# senior_project_rev4.net
KiCad netlist of a schematic drawn in EAGLE
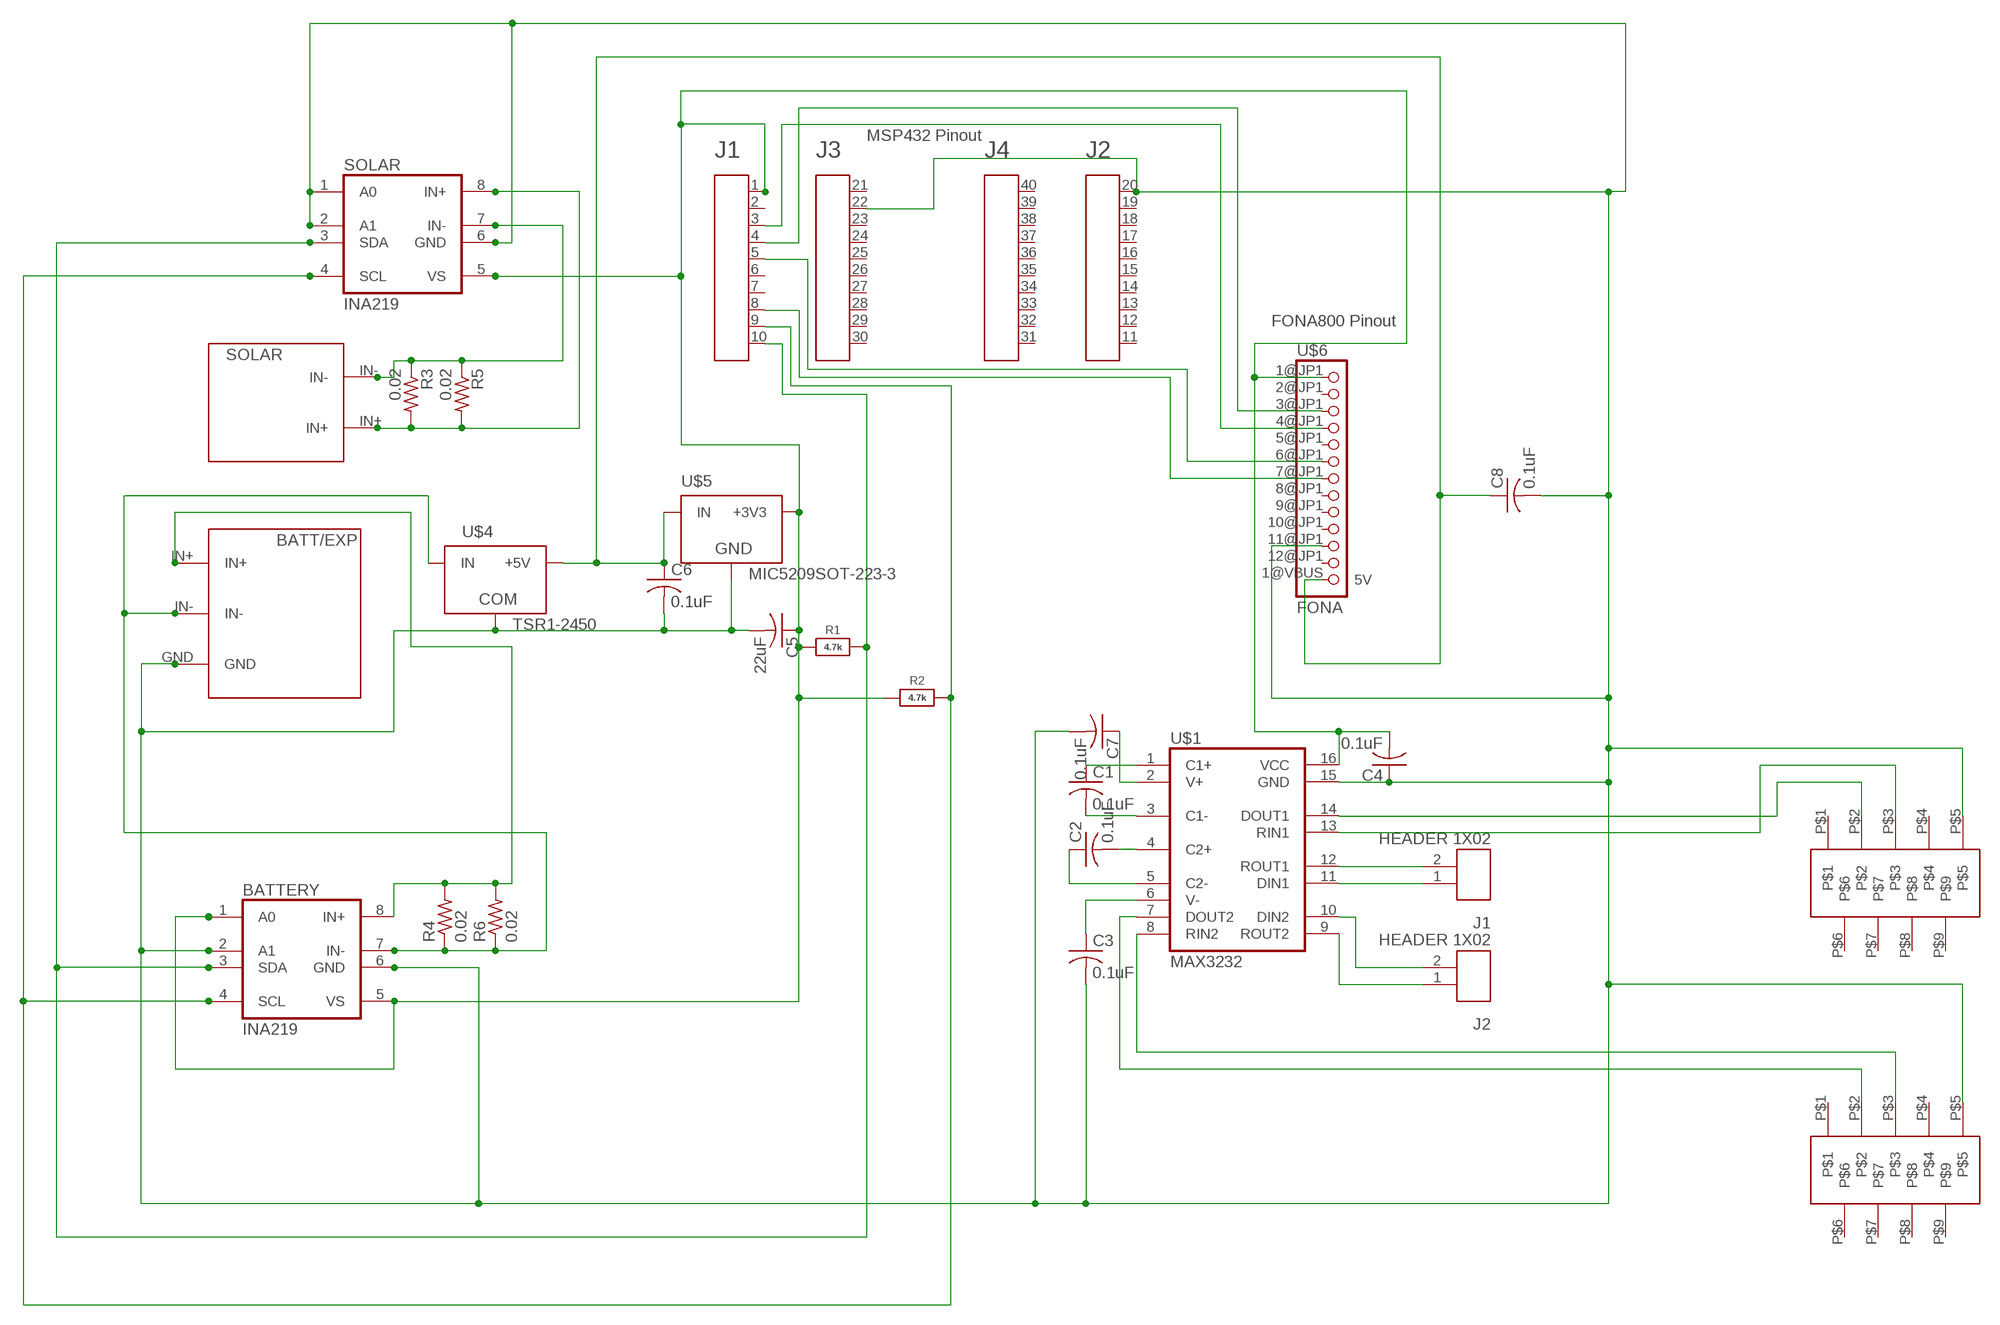
[diagram p0: schematic, sheet 1]

(export (version "E")
  (design (tool "Eeschema 10.0.6"))
  (components
    (comp (ref "A1")
      (value "MSP432")
      (footprint "eagle-import:4X10-BOOSTERPACK")
      (libsource (lib "eagle-import") (part "HEADER4X10-BOOSTERPACK"))
    )
    (comp (ref "BATTERY")
      (value "INA219")
      (footprint "eagle-import:SO08")
      (libsource (lib "eagle-import") (part "INA219"))
    )
    (comp (ref "C1")
      (value "0.1uF")
      (footprint "eagle-import:C1206")
      (libsource (lib "eagle-import") (part "resistor_C-USC1206"))
    )
    (comp (ref "C2")
      (value "0.1uF")
      (footprint "eagle-import:C1206")
      (libsource (lib "eagle-import") (part "resistor_C-USC1206"))
    )
    (comp (ref "C3")
      (value "0.1uF")
      (footprint "eagle-import:C1206")
      (libsource (lib "eagle-import") (part "resistor_C-USC1206"))
    )
    (comp (ref "C4")
      (value "0.1uF")
      (footprint "eagle-import:C1206")
      (libsource (lib "eagle-import") (part "resistor_C-USC1206"))
    )
    (comp (ref "C5")
      (value "22uF")
      (footprint "eagle-import:C1206")
      (libsource (lib "eagle-import") (part "C-USC1206"))
    )
    (comp (ref "C6")
      (value "0.1uF")
      (footprint "eagle-import:C1206")
      (libsource (lib "eagle-import") (part "C-USC1206"))
    )
    (comp (ref "C7")
      (value "0.1uF")
      (footprint "eagle-import:C1206")
      (libsource (lib "eagle-import") (part "C-USC1206"))
    )
    (comp (ref "C8")
      (value "0.1uF")
      (footprint "eagle-import:C1206")
      (libsource (lib "eagle-import") (part "C-USC1206"))
    )
    (comp (ref "J1")
      (value "HEADER 1X02")
      (footprint "eagle-import:1X02")
      (libsource (lib "eagle-import") (part "HEADER1X02_-TH100"))
    )
    (comp (ref "J2")
      (value "HEADER 1X02")
      (footprint "eagle-import:1X02")
      (libsource (lib "eagle-import") (part "HEADER1X02_-TH100"))
    )
    (comp (ref "R1")
      (value "4.7k")
      (footprint "eagle-import:_1206")
      (libsource (lib "eagle-import") (part "RESISTOR_1206"))
    )
    (comp (ref "R2")
      (value "4.7k")
      (footprint "eagle-import:_1206")
      (libsource (lib "eagle-import") (part "RESISTOR_1206"))
    )
    (comp (ref "R3")
      (value "0.02")
      (footprint "eagle-import:R2512")
      (libsource (lib "eagle-import") (part "R-US_R2512"))
    )
    (comp (ref "R4")
      (value "0.02")
      (footprint "eagle-import:R2512")
      (libsource (lib "eagle-import") (part "R-US_R2512"))
    )
    (comp (ref "R5")
      (value "0.02")
      (footprint "eagle-import:R2512")
      (libsource (lib "eagle-import") (part "R-US_R2512"))
    )
    (comp (ref "R6")
      (value "0.02")
      (footprint "eagle-import:R2512")
      (libsource (lib "eagle-import") (part "R-US_R2512"))
    )
    (comp (ref "RS232-1")
      (value "XM2C-9")
      (footprint "eagle-import:XM2C")
      (libsource (lib "eagle-import") (part "XM2C-9"))
    )
    (comp (ref "RS232-2")
      (value "XM2C-9")
      (footprint "eagle-import:XM2C")
      (libsource (lib "eagle-import") (part "XM2C-9"))
    )
    (comp (ref "SOLAR")
      (value "INA219")
      (footprint "eagle-import:SO08")
      (libsource (lib "eagle-import") (part "INA219"))
    )
    (comp (ref "U$1")
      (value "MAX3232")
      (footprint "eagle-import:SO16")
      (libsource (lib "eagle-import") (part "MAX3232"))
    )
    (comp (ref "U$2")
      (value "TERM-3")
      (footprint "eagle-import:TERM-3")
      (libsource (lib "eagle-import") (part "TERM-3"))
    )
    (comp (ref "U$3")
      (value "TERM-2")
      (footprint "eagle-import:TERM-2")
      (libsource (lib "eagle-import") (part "TERM-2"))
    )
    (comp (ref "U$4")
      (value "TSR1-2450")
      (footprint "eagle-import:TSR-1")
      (libsource (lib "eagle-import") (part "TSR1-2450"))
    )
    (comp (ref "U$5")
      (value "MIC5209SOT-223-3")
      (footprint "eagle-import:SOT-223")
      (libsource (lib "eagle-import") (part "MIC5209SOT-223-3"))
    )
    (comp (ref "U$6")
      (value "FONA")
      (footprint "eagle-import:JP1_ADAFRUIT-FONA-800-GSM-BREAKOUT")
      (libsource (lib "eagle-import") (part "FONA"))
    )
  )
  (nets
    (net (code "1") (name "Net-(A1-P$1)") (class "Default")
      (node (ref "A1") (pin "1") (pinfunction "P$1_1") (pintype "bidirectional"))
      (node (ref "BATTERY") (pin "1") (pinfunction "A0_1") (pintype "input"))
      (node (ref "BATTERY") (pin "5") (pinfunction "VS_5") (pintype "power_in"))
      (node (ref "C4") (pin "2") (pinfunction "2_2") (pintype "passive"))
      (node (ref "C5") (pin "1") (pinfunction "1_1") (pintype "passive"))
      (node (ref "R1") (pin "1") (pinfunction "1_1") (pintype "passive"))
      (node (ref "R2") (pin "1") (pinfunction "1_1") (pintype "passive"))
      (node (ref "SOLAR") (pin "5") (pinfunction "VS_5") (pintype "power_in"))
      (node (ref "U$1") (pin "16") (pinfunction "VCC_16") (pintype "output"))
      (node (ref "U$5") (pin "3") (pinfunction "+3V3_3") (pintype "power_in"))
      (node (ref "U$6") (pin "1@JP1") (pinfunction "VIO_1@JP1") (pintype "passive"))
    )
    (net (code "2") (name "Net-(A1-P$3)") (class "Default")
      (node (ref "A1") (pin "3") (pinfunction "P$3_3") (pintype "bidirectional"))
      (node (ref "U$6") (pin "4@JP1") (pinfunction "TX_4@JP1") (pintype "passive"))
    )
    (net (code "3") (name "Net-(A1-P$4)") (class "Default")
      (node (ref "A1") (pin "4") (pinfunction "P$4_4") (pintype "bidirectional"))
      (node (ref "U$6") (pin "3@JP1") (pinfunction "RX_3@JP1") (pintype "passive"))
    )
    (net (code "4") (name "Net-(A1-P$5)") (class "Default")
      (node (ref "A1") (pin "5") (pinfunction "P$5_5") (pintype "bidirectional"))
      (node (ref "U$6") (pin "6@JP1") (pinfunction "KEY_6@JP1") (pintype "passive"))
    )
    (net (code "5") (name "Net-(A1-P$8)") (class "Default")
      (node (ref "A1") (pin "8") (pinfunction "P$8_8") (pintype "bidirectional"))
      (node (ref "U$6") (pin "7@JP1") (pinfunction "PS_7@JP1") (pintype "passive"))
    )
    (net (code "6") (name "Net-(A1-P$9)") (class "Default")
      (node (ref "A1") (pin "9") (pinfunction "P$9_9") (pintype "bidirectional"))
      (node (ref "BATTERY") (pin "4") (pinfunction "SCL_4") (pintype "bidirectional"))
      (node (ref "R2") (pin "2") (pinfunction "2_2") (pintype "passive"))
      (node (ref "SOLAR") (pin "4") (pinfunction "SCL_4") (pintype "bidirectional"))
    )
    (net (code "7") (name "Net-(A1-P$10)") (class "Default")
      (node (ref "A1") (pin "10") (pinfunction "P$10_10") (pintype "bidirectional"))
      (node (ref "BATTERY") (pin "3") (pinfunction "SDA_3") (pintype "bidirectional"))
      (node (ref "R1") (pin "2") (pinfunction "2_2") (pintype "passive"))
      (node (ref "SOLAR") (pin "3") (pinfunction "SDA_3") (pintype "bidirectional"))
    )
    (net (code "8") (name "Net-(A1-P$20)") (class "Default")
      (node (ref "A1") (pin "20") (pinfunction "P$20_20") (pintype "bidirectional"))
      (node (ref "A1") (pin "22") (pinfunction "P$22_22") (pintype "bidirectional"))
      (node (ref "BATTERY") (pin "2") (pinfunction "A1_2") (pintype "input"))
      (node (ref "BATTERY") (pin "6") (pinfunction "GND_6") (pintype "power_in"))
      (node (ref "C3") (pin "2") (pinfunction "2_2") (pintype "passive"))
      (node (ref "C4") (pin "1") (pinfunction "1_1") (pintype "passive"))
      (node (ref "C5") (pin "2") (pinfunction "2_2") (pintype "passive"))
      (node (ref "C6") (pin "2") (pinfunction "2_2") (pintype "passive"))
      (node (ref "C7") (pin "2") (pinfunction "2_2") (pintype "passive"))
      (node (ref "C8") (pin "2") (pinfunction "2_2") (pintype "passive"))
      (node (ref "RS232-1") (pin "P$5") (pinfunction "P$5_P$5") (pintype "bidirectional"))
      (node (ref "RS232-2") (pin "P$5") (pinfunction "P$5_P$5") (pintype "bidirectional"))
      (node (ref "SOLAR") (pin "1") (pinfunction "A0_1") (pintype "input"))
      (node (ref "SOLAR") (pin "2") (pinfunction "A1_2") (pintype "input"))
      (node (ref "SOLAR") (pin "6") (pinfunction "GND_6") (pintype "power_in"))
      (node (ref "U$1") (pin "15") (pinfunction "GND_15") (pintype "output"))
      (node (ref "U$2") (pin "GND") (pinfunction "GND_GND") (pintype "power_in"))
      (node (ref "U$4") (pin "2") (pinfunction "COM_2") (pintype "power_in"))
      (node (ref "U$5") (pin "2") (pinfunction "GND_2") (pintype "power_in"))
      (node (ref "U$5") (pin "4") (pinfunction "GND_4") (pintype "power_in"))
      (node (ref "U$6") (pin "11@JP1") (pinfunction "GND_11@JP1") (pintype "passive"))
    )
    (net (code "9") (name "Net-(BATTERY-IN+)") (class "Default")
      (node (ref "BATTERY") (pin "8") (pinfunction "IN+_8") (pintype "input"))
      (node (ref "R4") (pin "2") (pinfunction "2_2") (pintype "passive"))
      (node (ref "R6") (pin "2") (pinfunction "2_2") (pintype "passive"))
      (node (ref "U$2") (pin "IN+") (pinfunction "IN+_IN+") (pintype "power_in"))
    )
    (net (code "10") (name "Net-(BATTERY-IN-)") (class "Default")
      (node (ref "BATTERY") (pin "7") (pinfunction "IN-_7") (pintype "input"))
      (node (ref "R4") (pin "1") (pinfunction "1_1") (pintype "passive"))
      (node (ref "R6") (pin "1") (pinfunction "1_1") (pintype "passive"))
      (node (ref "U$2") (pin "IN-") (pinfunction "IN-_IN-") (pintype "power_in"))
      (node (ref "U$4") (pin "1") (pinfunction "IN_1") (pintype "power_in"))
    )
    (net (code "11") (name "Net-(SOLAR-IN+)") (class "Default")
      (node (ref "R3") (pin "2") (pinfunction "2_2") (pintype "passive"))
      (node (ref "R5") (pin "2") (pinfunction "2_2") (pintype "passive"))
      (node (ref "SOLAR") (pin "8") (pinfunction "IN+_8") (pintype "input"))
      (node (ref "U$3") (pin "IN+") (pinfunction "IN+_IN+") (pintype "passive"))
    )
    (net (code "12") (name "Net-(SOLAR-IN-)") (class "Default")
      (node (ref "R3") (pin "1") (pinfunction "1_1") (pintype "passive"))
      (node (ref "R5") (pin "1") (pinfunction "1_1") (pintype "passive"))
      (node (ref "SOLAR") (pin "7") (pinfunction "IN-_7") (pintype "input"))
      (node (ref "U$3") (pin "IN-") (pinfunction "IN-_IN-") (pintype "passive"))
    )
    (net (code "13") (name "Net-(U$1-C1+)") (class "Default")
      (node (ref "C1") (pin "1") (pinfunction "1_1") (pintype "passive"))
      (node (ref "U$1") (pin "1") (pinfunction "C1+_1") (pintype "input"))
    )
    (net (code "14") (name "Net-(U$1-C1-)") (class "Default")
      (node (ref "C1") (pin "2") (pinfunction "2_2") (pintype "passive"))
      (node (ref "U$1") (pin "3") (pinfunction "C1-_3") (pintype "input"))
    )
    (net (code "15") (name "Net-(U$1-C2+)") (class "Default")
      (node (ref "C2") (pin "2") (pinfunction "2_2") (pintype "passive"))
      (node (ref "U$1") (pin "4") (pinfunction "C2+_4") (pintype "input"))
    )
    (net (code "16") (name "Net-(U$1-C2-)") (class "Default")
      (node (ref "C2") (pin "1") (pinfunction "1_1") (pintype "passive"))
      (node (ref "U$1") (pin "5") (pinfunction "C2-_5") (pintype "bidirectional"))
    )
    (net (code "17") (name "Net-(U$1-DIN1)") (class "Default")
      (node (ref "J1") (pin "1") (pinfunction "1_1") (pintype "bidirectional"))
      (node (ref "U$1") (pin "11") (pinfunction "DIN1_11") (pintype "bidirectional"))
    )
    (net (code "18") (name "Net-(U$1-DIN2)") (class "Default")
      (node (ref "J2") (pin "2") (pinfunction "2_2") (pintype "bidirectional"))
      (node (ref "U$1") (pin "10") (pinfunction "DIN2_10") (pintype "bidirectional"))
    )
    (net (code "19") (name "Net-(U$1-DOUT1)") (class "Default")
      (node (ref "RS232-1") (pin "P$2") (pinfunction "P$2_P$2") (pintype "bidirectional"))
      (node (ref "U$1") (pin "14") (pinfunction "DOUT1_14") (pintype "bidirectional"))
    )
    (net (code "20") (name "Net-(U$1-DOUT2)") (class "Default")
      (node (ref "RS232-2") (pin "P$2") (pinfunction "P$2_P$2") (pintype "bidirectional"))
      (node (ref "U$1") (pin "7") (pinfunction "DOUT2_7") (pintype "bidirectional"))
    )
    (net (code "21") (name "Net-(U$1-RIN1)") (class "Default")
      (node (ref "RS232-1") (pin "P$3") (pinfunction "P$3_P$3") (pintype "bidirectional"))
      (node (ref "U$1") (pin "13") (pinfunction "RIN1_13") (pintype "bidirectional"))
    )
    (net (code "22") (name "Net-(U$1-RIN2)") (class "Default")
      (node (ref "RS232-2") (pin "P$3") (pinfunction "P$3_P$3") (pintype "bidirectional"))
      (node (ref "U$1") (pin "8") (pinfunction "RIN2_8") (pintype "bidirectional"))
    )
    (net (code "23") (name "Net-(U$1-ROUT1)") (class "Default")
      (node (ref "J1") (pin "2") (pinfunction "2_2") (pintype "bidirectional"))
      (node (ref "U$1") (pin "12") (pinfunction "ROUT1_12") (pintype "bidirectional"))
    )
    (net (code "24") (name "Net-(U$1-ROUT2)") (class "Default")
      (node (ref "J2") (pin "1") (pinfunction "1_1") (pintype "bidirectional"))
      (node (ref "U$1") (pin "9") (pinfunction "ROUT2_9") (pintype "bidirectional"))
    )
    (net (code "25") (name "Net-(U$1-V+)") (class "Default")
      (node (ref "C7") (pin "1") (pinfunction "1_1") (pintype "passive"))
      (node (ref "U$1") (pin "2") (pinfunction "V+_2") (pintype "input"))
    )
    (net (code "26") (name "Net-(U$1-V-)") (class "Default")
      (node (ref "C3") (pin "1") (pinfunction "1_1") (pintype "passive"))
      (node (ref "U$1") (pin "6") (pinfunction "V-_6") (pintype "bidirectional"))
    )
    (net (code "27") (name "Net-(U$4-+5V)") (class "Default")
      (node (ref "C6") (pin "1") (pinfunction "1_1") (pintype "passive"))
      (node (ref "C8") (pin "1") (pinfunction "1_1") (pintype "passive"))
      (node (ref "U$4") (pin "3") (pinfunction "+5V_3") (pintype "power_in"))
      (node (ref "U$5") (pin "1") (pinfunction "IN_1") (pintype "power_in"))
      (node (ref "U$6") (pin "1@VBUS") (pinfunction "5V_1@VBUS") (pintype "passive"))
    )
    (net (code "28") (name "unconnected-(A1-P$2-Pad2)") (class "Default")
      (node (ref "A1") (pin "2") (pinfunction "P$2_2") (pintype "bidirectional"))
    )
    (net (code "29") (name "unconnected-(A1-P$6-Pad6)") (class "Default")
      (node (ref "A1") (pin "6") (pinfunction "P$6_6") (pintype "bidirectional"))
    )
    (net (code "30") (name "unconnected-(A1-P$7-Pad7)") (class "Default")
      (node (ref "A1") (pin "7") (pinfunction "P$7_7") (pintype "bidirectional"))
    )
    (net (code "31") (name "unconnected-(A1-P$11-Pad11)") (class "Default")
      (node (ref "A1") (pin "11") (pinfunction "P$11_11") (pintype "bidirectional"))
    )
    (net (code "32") (name "unconnected-(A1-P$12-Pad12)") (class "Default")
      (node (ref "A1") (pin "12") (pinfunction "P$12_12") (pintype "bidirectional"))
    )
    (net (code "33") (name "unconnected-(A1-P$13-Pad13)") (class "Default")
      (node (ref "A1") (pin "13") (pinfunction "P$13_13") (pintype "bidirectional"))
    )
    (net (code "34") (name "unconnected-(A1-P$14-Pad14)") (class "Default")
      (node (ref "A1") (pin "14") (pinfunction "P$14_14") (pintype "bidirectional"))
    )
    (net (code "35") (name "unconnected-(A1-P$15-Pad15)") (class "Default")
      (node (ref "A1") (pin "15") (pinfunction "P$15_15") (pintype "bidirectional"))
    )
    (net (code "36") (name "unconnected-(A1-P$16-Pad16)") (class "Default")
      (node (ref "A1") (pin "16") (pinfunction "P$16_16") (pintype "bidirectional"))
    )
    (net (code "37") (name "unconnected-(A1-P$17-Pad17)") (class "Default")
      (node (ref "A1") (pin "17") (pinfunction "P$17_17") (pintype "bidirectional"))
    )
    (net (code "38") (name "unconnected-(A1-P$18-Pad18)") (class "Default")
      (node (ref "A1") (pin "18") (pinfunction "P$18_18") (pintype "bidirectional"))
    )
    (net (code "39") (name "unconnected-(A1-P$19-Pad19)") (class "Default")
      (node (ref "A1") (pin "19") (pinfunction "P$19_19") (pintype "bidirectional"))
    )
    (net (code "40") (name "unconnected-(A1-P$21-Pad21)") (class "Default")
      (node (ref "A1") (pin "21") (pinfunction "P$21_21") (pintype "bidirectional"))
    )
    (net (code "41") (name "unconnected-(A1-P$23-Pad23)") (class "Default")
      (node (ref "A1") (pin "23") (pinfunction "P$23_23") (pintype "bidirectional"))
    )
    (net (code "42") (name "unconnected-(A1-P$24-Pad24)") (class "Default")
      (node (ref "A1") (pin "24") (pinfunction "P$24_24") (pintype "bidirectional"))
    )
    (net (code "43") (name "unconnected-(A1-P$25-Pad25)") (class "Default")
      (node (ref "A1") (pin "25") (pinfunction "P$25_25") (pintype "bidirectional"))
    )
    (net (code "44") (name "unconnected-(A1-P$26-Pad26)") (class "Default")
      (node (ref "A1") (pin "26") (pinfunction "P$26_26") (pintype "bidirectional"))
    )
    (net (code "45") (name "unconnected-(A1-P$27-Pad27)") (class "Default")
      (node (ref "A1") (pin "27") (pinfunction "P$27_27") (pintype "bidirectional"))
    )
    (net (code "46") (name "unconnected-(A1-P$28-Pad28)") (class "Default")
      (node (ref "A1") (pin "28") (pinfunction "P$28_28") (pintype "bidirectional"))
    )
    (net (code "47") (name "unconnected-(A1-P$29-Pad29)") (class "Default")
      (node (ref "A1") (pin "29") (pinfunction "P$29_29") (pintype "bidirectional"))
    )
    (net (code "48") (name "unconnected-(A1-P$30-Pad30)") (class "Default")
      (node (ref "A1") (pin "30") (pinfunction "P$30_30") (pintype "bidirectional"))
    )
    (net (code "49") (name "unconnected-(A1-P$31-Pad31)") (class "Default")
      (node (ref "A1") (pin "31") (pinfunction "P$31_31") (pintype "bidirectional"))
    )
    (net (code "50") (name "unconnected-(A1-P$32-Pad32)") (class "Default")
      (node (ref "A1") (pin "32") (pinfunction "P$32_32") (pintype "bidirectional"))
    )
    (net (code "51") (name "unconnected-(A1-P$33-Pad33)") (class "Default")
      (node (ref "A1") (pin "33") (pinfunction "P$33_33") (pintype "bidirectional"))
    )
    (net (code "52") (name "unconnected-(A1-P$34-Pad34)") (class "Default")
      (node (ref "A1") (pin "34") (pinfunction "P$34_34") (pintype "bidirectional"))
    )
    (net (code "53") (name "unconnected-(A1-P$35-Pad35)") (class "Default")
      (node (ref "A1") (pin "35") (pinfunction "P$35_35") (pintype "bidirectional"))
    )
    (net (code "54") (name "unconnected-(A1-P$36-Pad36)") (class "Default")
      (node (ref "A1") (pin "36") (pinfunction "P$36_36") (pintype "bidirectional"))
    )
    (net (code "55") (name "unconnected-(A1-P$37-Pad37)") (class "Default")
      (node (ref "A1") (pin "37") (pinfunction "P$37_37") (pintype "bidirectional"))
    )
    (net (code "56") (name "unconnected-(A1-P$38-Pad38)") (class "Default")
      (node (ref "A1") (pin "38") (pinfunction "P$38_38") (pintype "bidirectional"))
    )
    (net (code "57") (name "unconnected-(A1-P$39-Pad39)") (class "Default")
      (node (ref "A1") (pin "39") (pinfunction "P$39_39") (pintype "bidirectional"))
    )
    (net (code "58") (name "unconnected-(A1-P$40-Pad40)") (class "Default")
      (node (ref "A1") (pin "40") (pinfunction "P$40_40") (pintype "bidirectional"))
    )
    (net (code "59") (name "unconnected-(RS232-1-PadP$1)") (class "Default")
      (node (ref "RS232-1") (pin "P$1") (pinfunction "P$1_P$1") (pintype "bidirectional"))
    )
    (net (code "60") (name "unconnected-(RS232-1-PadP$4)") (class "Default")
      (node (ref "RS232-1") (pin "P$4") (pinfunction "P$4_P$4") (pintype "bidirectional"))
    )
    (net (code "61") (name "unconnected-(RS232-1-PadP$6)") (class "Default")
      (node (ref "RS232-1") (pin "P$6") (pinfunction "P$6_P$6") (pintype "bidirectional"))
    )
    (net (code "62") (name "unconnected-(RS232-1-PadP$7)") (class "Default")
      (node (ref "RS232-1") (pin "P$7") (pinfunction "P$7_P$7") (pintype "bidirectional"))
    )
    (net (code "63") (name "unconnected-(RS232-1-PadP$8)") (class "Default")
      (node (ref "RS232-1") (pin "P$8") (pinfunction "P$8_P$8") (pintype "bidirectional"))
    )
    (net (code "64") (name "unconnected-(RS232-1-PadP$9)") (class "Default")
      (node (ref "RS232-1") (pin "P$9") (pinfunction "P$9_P$9") (pintype "bidirectional"))
    )
    (net (code "65") (name "unconnected-(RS232-2-PadP$1)") (class "Default")
      (node (ref "RS232-2") (pin "P$1") (pinfunction "P$1_P$1") (pintype "bidirectional"))
    )
    (net (code "66") (name "unconnected-(RS232-2-PadP$4)") (class "Default")
      (node (ref "RS232-2") (pin "P$4") (pinfunction "P$4_P$4") (pintype "bidirectional"))
    )
    (net (code "67") (name "unconnected-(RS232-2-PadP$6)") (class "Default")
      (node (ref "RS232-2") (pin "P$6") (pinfunction "P$6_P$6") (pintype "bidirectional"))
    )
    (net (code "68") (name "unconnected-(RS232-2-PadP$7)") (class "Default")
      (node (ref "RS232-2") (pin "P$7") (pinfunction "P$7_P$7") (pintype "bidirectional"))
    )
    (net (code "69") (name "unconnected-(RS232-2-PadP$8)") (class "Default")
      (node (ref "RS232-2") (pin "P$8") (pinfunction "P$8_P$8") (pintype "bidirectional"))
    )
    (net (code "70") (name "unconnected-(RS232-2-PadP$9)") (class "Default")
      (node (ref "RS232-2") (pin "P$9") (pinfunction "P$9_P$9") (pintype "bidirectional"))
    )
    (net (code "71") (name "unconnected-(U$6-BAT-Pad12@JP1)") (class "Default")
      (node (ref "U$6") (pin "12@JP1") (pinfunction "BAT_12@JP1") (pintype "passive"))
    )
    (net (code "72") (name "unconnected-(U$6-NS-Pad2@JP1)") (class "Default")
      (node (ref "U$6") (pin "2@JP1") (pinfunction "NS_2@JP1") (pintype "passive"))
    )
    (net (code "73") (name "unconnected-(U$6-RI-Pad5@JP1)") (class "Default")
      (node (ref "U$6") (pin "5@JP1") (pinfunction "RI_5@JP1") (pintype "passive"))
    )
    (net (code "74") (name "unconnected-(U$6-RST-Pad8@JP1)") (class "Default")
      (node (ref "U$6") (pin "8@JP1") (pinfunction "RST_8@JP1") (pintype "passive"))
    )
    (net (code "75") (name "unconnected-(U$6-SPKR+-Pad10@JP1)") (class "Default")
      (node (ref "U$6") (pin "10@JP1") (pinfunction "SPKR+_10@JP1") (pintype "passive"))
    )
    (net (code "76") (name "unconnected-(U$6-SPRK--Pad9@JP1)") (class "Default")
      (node (ref "U$6") (pin "9@JP1") (pinfunction "SPRK-_9@JP1") (pintype "passive"))
    )
  )
)
